# Shield_delitel.net
KiCad netlist of a schematic drawn in Altium Designer
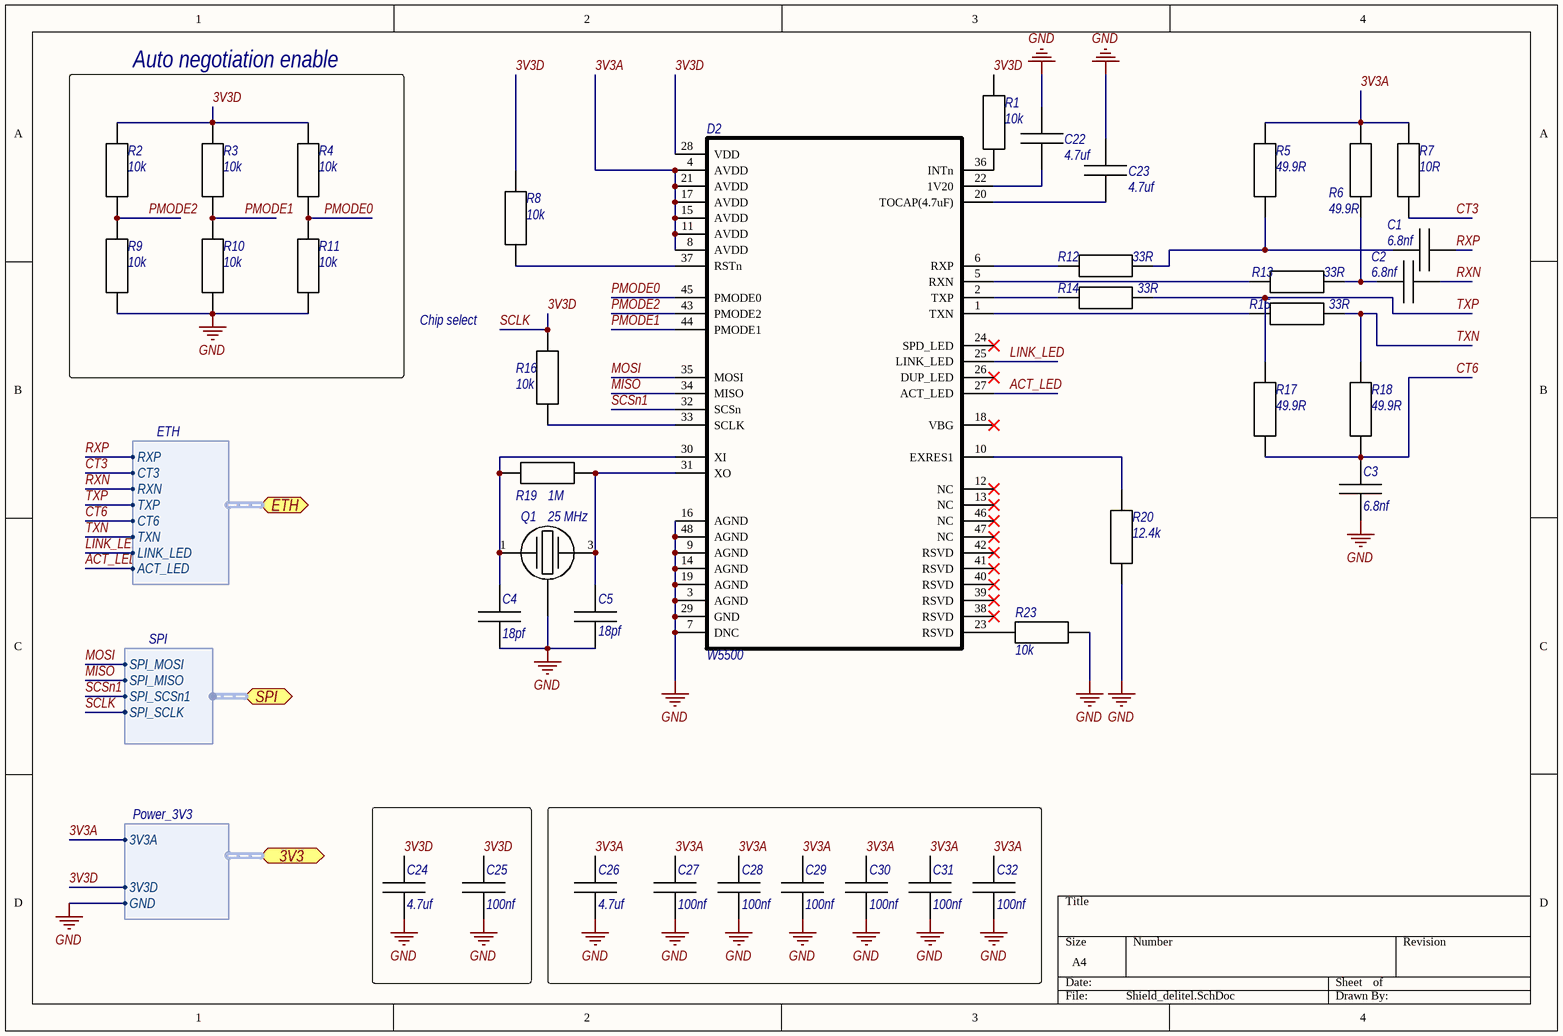
[diagram p0: Shield_delitel.SchDoc]

(export (version "E")
  (design (tool "Eeschema 10.0.6"))
  (components
    (comp (ref "C1") (value "6.8nf") (libsource (lib "Passive") (part "Capacitor")))
    (comp (ref "C2") (value "6.8nf") (libsource (lib "Passive") (part "Capacitor")))
    (comp (ref "C3") (value "6.8nf") (libsource (lib "Passive") (part "Capacitor")))
    (comp (ref "C4") (value "18pf") (libsource (lib "Passive") (part "Capacitor")))
    (comp (ref "C5") (value "18pf") (libsource (lib "Passive") (part "Capacitor")))
    (comp (ref "C22") (value "4.7uf") (libsource (lib "Passive") (part "Capacitor")))
    (comp (ref "C23") (value "4.7uf") (libsource (lib "Passive") (part "Capacitor")))
    (comp (ref "C24") (value "4.7uf") (libsource (lib "Passive") (part "Capacitor")))
    (comp (ref "C25") (value "100nf") (libsource (lib "Passive") (part "Capacitor")))
    (comp (ref "C26") (value "4.7uf") (libsource (lib "Passive") (part "Capacitor")))
    (comp (ref "C27") (value "100nf") (libsource (lib "Passive") (part "Capacitor")))
    (comp (ref "C28") (value "100nf") (libsource (lib "Passive") (part "Capacitor")))
    (comp (ref "C29") (value "100nf") (libsource (lib "Passive") (part "Capacitor")))
    (comp (ref "C30") (value "100nf") (libsource (lib "Passive") (part "Capacitor")))
    (comp (ref "C31") (value "100nf") (libsource (lib "Passive") (part "Capacitor")))
    (comp (ref "C32") (value "100nf") (libsource (lib "Passive") (part "Capacitor")))
    (comp (ref "D2")
      (value "W5500")
      (footprint "LQFP-48 7.0 x 7.0 x 1.6")
      (libsource (lib "ic") (part "W5500"))
    )
    (comp (ref "Q1") (value "25 MHz") (libsource (lib "Passive") (part "Oscillator")))
    (comp (ref "R1") (value "10k") (description "Resistor") (libsource (lib "") (part "Resistor_1")))
    (comp (ref "R2") (value "10k") (description "Resistor") (libsource (lib "") (part "Resistor_1")))
    (comp (ref "R3") (value "10k") (description "Resistor") (libsource (lib "") (part "Resistor_1")))
    (comp (ref "R4") (value "10k") (description "Resistor") (libsource (lib "") (part "Resistor_1")))
    (comp (ref "R5") (value "49.9R") (description "Resistor") (libsource (lib "Passive") (part "Resistor")))
    (comp (ref "R6") (value "49.9R") (description "Resistor") (libsource (lib "Passive") (part "Resistor")))
    (comp (ref "R7") (value "10R") (description "Resistor") (libsource (lib "Passive") (part "Resistor")))
    (comp (ref "R8") (value "10k") (description "Resistor") (libsource (lib "") (part "Resistor_1")))
    (comp (ref "R9") (value "10k") (description "Resistor") (libsource (lib "") (part "Resistor_1")))
    (comp (ref "R10") (value "10k") (description "Resistor") (libsource (lib "") (part "Resistor_1")))
    (comp (ref "R11") (value "10k") (description "Resistor") (libsource (lib "") (part "Resistor_1")))
    (comp (ref "R12") (value "33R") (description "Resistor") (libsource (lib "") (part "Resistor_2")))
    (comp (ref "R13") (value "33R") (description "Resistor") (libsource (lib "") (part "Resistor_2")))
    (comp (ref "R14") (value "33R") (description "Resistor") (libsource (lib "") (part "Resistor_2")))
    (comp (ref "R15") (value "33R") (description "Resistor") (libsource (lib "") (part "Resistor_2")))
    (comp (ref "R16") (value "10k") (description "Resistor") (libsource (lib "Passive") (part "Resistor")))
    (comp (ref "R17") (value "49.9R") (description "Resistor") (libsource (lib "Passive") (part "Resistor")))
    (comp (ref "R18") (value "49.9R") (description "Resistor") (libsource (lib "Passive") (part "Resistor")))
    (comp (ref "R19") (value "1M") (description "Resistor") (libsource (lib "") (part "Resistor_2")))
    (comp (ref "R20") (value "12.4k") (description "Resistor") (libsource (lib "") (part "Resistor_1")))
    (comp (ref "R23") (value "10k") (description "Resistor") (libsource (lib "") (part "Resistor_2")))
  )
  (nets
    (net (code "4") (name "/3V3A") (class "Default")
      (node (ref "C26") (pin "2") (pinfunction "2_2") (pintype "passive"))
      (node (ref "C27") (pin "2") (pinfunction "2_2") (pintype "passive"))
      (node (ref "C28") (pin "2") (pinfunction "2_2") (pintype "passive"))
      (node (ref "C29") (pin "2") (pinfunction "2_2") (pintype "passive"))
      (node (ref "C30") (pin "2") (pinfunction "2_2") (pintype "passive"))
      (node (ref "C31") (pin "2") (pinfunction "2_2") (pintype "passive"))
      (node (ref "C32") (pin "2") (pinfunction "2_2") (pintype "passive"))
      (node (ref "D2") (pin "11") (pinfunction "AVDD_11") (pintype "passive"))
      (node (ref "D2") (pin "15") (pinfunction "AVDD_15") (pintype "passive"))
      (node (ref "D2") (pin "17") (pinfunction "AVDD_17") (pintype "passive"))
      (node (ref "D2") (pin "21") (pinfunction "AVDD_21") (pintype "passive"))
      (node (ref "D2") (pin "4") (pinfunction "AVDD_4") (pintype "passive"))
      (node (ref "D2") (pin "8") (pinfunction "AVDD_8") (pintype "passive"))
      (node (ref "R5") (pin "1") (pinfunction "1_1") (pintype "passive"))
      (node (ref "R6") (pin "1") (pinfunction "1_1") (pintype "passive"))
      (node (ref "R7") (pin "1") (pinfunction "1_1") (pintype "passive"))
    )
    (net (code "5") (name "/3V3D") (class "Default")
      (node (ref "C24") (pin "2") (pinfunction "2_2") (pintype "passive"))
      (node (ref "C25") (pin "2") (pinfunction "2_2") (pintype "passive"))
      (node (ref "D2") (pin "28") (pinfunction "VDD_28") (pintype "passive"))
      (node (ref "R1") (pin "2") (pinfunction "2_2") (pintype "passive"))
      (node (ref "R16") (pin "1") (pinfunction "1_1") (pintype "passive"))
      (node (ref "R2") (pin "2") (pinfunction "2_2") (pintype "passive"))
      (node (ref "R3") (pin "2") (pinfunction "2_2") (pintype "passive"))
      (node (ref "R4") (pin "2") (pinfunction "2_2") (pintype "passive"))
      (node (ref "R8") (pin "2") (pinfunction "2_2") (pintype "passive"))
    )
    (net (code "6") (name "/ACT_LED") (class "Default")
      (node (ref "D2") (pin "27") (pinfunction "ACT_LED_27") (pintype "passive"))
    )
    (net (code "7") (name "/CT3") (class "Default")
      (node (ref "R7") (pin "2") (pinfunction "2_2") (pintype "passive"))
    )
    (net (code "8") (name "/CT6") (class "Default")
      (node (ref "C3") (pin "2") (pinfunction "2_2") (pintype "passive"))
      (node (ref "R17") (pin "2") (pinfunction "2_2") (pintype "passive"))
      (node (ref "R18") (pin "2") (pinfunction "2_2") (pintype "passive"))
    )
    (net (code "9") (name "/LINK_LED") (class "Default")
      (node (ref "D2") (pin "25") (pinfunction "LINK_LED_25") (pintype "passive"))
    )
    (net (code "10") (name "/MISO") (class "Default")
      (node (ref "D2") (pin "34") (pinfunction "MISO_34") (pintype "passive"))
    )
    (net (code "11") (name "/MOSI") (class "Default")
      (node (ref "D2") (pin "35") (pinfunction "MOSI_35") (pintype "passive"))
    )
    (net (code "12") (name "/PMODE0") (class "Default")
      (node (ref "D2") (pin "45") (pinfunction "PMODE0_45") (pintype "passive"))
      (node (ref "R11") (pin "2") (pinfunction "2_2") (pintype "passive"))
      (node (ref "R4") (pin "1") (pinfunction "1_1") (pintype "passive"))
    )
    (net (code "13") (name "/PMODE1") (class "Default")
      (node (ref "D2") (pin "44") (pinfunction "PMODE1_44") (pintype "passive"))
      (node (ref "R10") (pin "2") (pinfunction "2_2") (pintype "passive"))
      (node (ref "R3") (pin "1") (pinfunction "1_1") (pintype "passive"))
    )
    (net (code "14") (name "/PMODE2") (class "Default")
      (node (ref "D2") (pin "43") (pinfunction "PMODE2_43") (pintype "passive"))
      (node (ref "R2") (pin "1") (pinfunction "1_1") (pintype "passive"))
      (node (ref "R9") (pin "2") (pinfunction "2_2") (pintype "passive"))
    )
    (net (code "15") (name "/RXN") (class "Default")
      (node (ref "C2") (pin "1") (pinfunction "1_1") (pintype "passive"))
    )
    (net (code "16") (name "/RXP") (class "Default")
      (node (ref "C1") (pin "1") (pinfunction "1_1") (pintype "passive"))
    )
    (net (code "17") (name "/SCSn1") (class "Default")
      (node (ref "D2") (pin "32") (pinfunction "SCSn_32") (pintype "passive"))
    )
    (net (code "18") (name "/TXN") (class "Default")
      (node (ref "R15") (pin "1") (pinfunction "1_1") (pintype "passive"))
      (node (ref "R18") (pin "1") (pinfunction "1_1") (pintype "passive"))
    )
    (net (code "19") (name "/TXP") (class "Default")
      (node (ref "R14") (pin "1") (pinfunction "1_1") (pintype "passive"))
      (node (ref "R17") (pin "1") (pinfunction "1_1") (pintype "passive"))
    )
    (net (code "23") (name "GND") (class "Default")
      (node (ref "C22") (pin "1") (pinfunction "1_1") (pintype "passive"))
      (node (ref "C23") (pin "1") (pinfunction "1_1") (pintype "passive"))
      (node (ref "C24") (pin "1") (pinfunction "1_1") (pintype "passive"))
      (node (ref "C25") (pin "1") (pinfunction "1_1") (pintype "passive"))
      (node (ref "C26") (pin "1") (pinfunction "1_1") (pintype "passive"))
      (node (ref "C27") (pin "1") (pinfunction "1_1") (pintype "passive"))
      (node (ref "C28") (pin "1") (pinfunction "1_1") (pintype "passive"))
      (node (ref "C29") (pin "1") (pinfunction "1_1") (pintype "passive"))
      (node (ref "C3") (pin "1") (pinfunction "1_1") (pintype "passive"))
      (node (ref "C30") (pin "1") (pinfunction "1_1") (pintype "passive"))
      (node (ref "C31") (pin "1") (pinfunction "1_1") (pintype "passive"))
      (node (ref "C32") (pin "1") (pinfunction "1_1") (pintype "passive"))
      (node (ref "C4") (pin "1") (pinfunction "1_1") (pintype "passive"))
      (node (ref "C5") (pin "1") (pinfunction "1_1") (pintype "passive"))
      (node (ref "D2") (pin "14") (pinfunction "AGND_14") (pintype "passive"))
      (node (ref "D2") (pin "16") (pinfunction "AGND_16") (pintype "passive"))
      (node (ref "D2") (pin "19") (pinfunction "AGND_19") (pintype "passive"))
      (node (ref "D2") (pin "29") (pinfunction "GND_29") (pintype "passive"))
      (node (ref "D2") (pin "3") (pinfunction "AGND_3") (pintype "passive"))
      (node (ref "D2") (pin "48") (pinfunction "AGND_48") (pintype "passive"))
      (node (ref "D2") (pin "7") (pinfunction "DNC_7") (pintype "passive"))
      (node (ref "D2") (pin "9") (pinfunction "AGND_9") (pintype "passive"))
      (node (ref "Q1") (pin "2") (pinfunction "2_2") (pintype "passive"))
      (node (ref "Q1") (pin "4") (pinfunction "4_4") (pintype "passive"))
      (node (ref "R10") (pin "1") (pinfunction "1_1") (pintype "passive"))
      (node (ref "R11") (pin "1") (pinfunction "1_1") (pintype "passive"))
      (node (ref "R20") (pin "1") (pinfunction "1_1") (pintype "passive"))
      (node (ref "R23") (pin "1") (pinfunction "1_1") (pintype "passive"))
      (node (ref "R9") (pin "1") (pinfunction "1_1") (pintype "passive"))
    )
    (net (code "24") (name "Net-(C1-Pad2)") (class "Default")
      (node (ref "C1") (pin "2") (pinfunction "2_2") (pintype "passive"))
      (node (ref "R12") (pin "1") (pinfunction "1_1") (pintype "passive"))
      (node (ref "R5") (pin "2") (pinfunction "2_2") (pintype "passive"))
    )
    (net (code "25") (name "Net-(C2-Pad2)") (class "Default")
      (node (ref "C2") (pin "2") (pinfunction "2_2") (pintype "passive"))
      (node (ref "R13") (pin "1") (pinfunction "1_1") (pintype "passive"))
      (node (ref "R6") (pin "2") (pinfunction "2_2") (pintype "passive"))
    )
    (net (code "26") (name "Net-(D2-1V20)") (class "Default")
      (node (ref "C22") (pin "2") (pinfunction "2_2") (pintype "passive"))
      (node (ref "D2") (pin "22") (pinfunction "1V20_22") (pintype "passive"))
    )
    (net (code "27") (name "Net-(D2-EXRES1)") (class "Default")
      (node (ref "D2") (pin "10") (pinfunction "EXRES1_10") (pintype "passive"))
      (node (ref "R20") (pin "2") (pinfunction "2_2") (pintype "passive"))
    )
    (net (code "28") (name "Net-(D2-INTn)") (class "Default")
      (node (ref "D2") (pin "36") (pinfunction "INTn_36") (pintype "passive"))
      (node (ref "R1") (pin "1") (pinfunction "1_1") (pintype "passive"))
    )
    (net (code "29") (name "Net-(D2-RSTn)") (class "Default")
      (node (ref "D2") (pin "37") (pinfunction "RSTn_37") (pintype "passive"))
      (node (ref "R8") (pin "1") (pinfunction "1_1") (pintype "passive"))
    )
    (net (code "30") (name "Net-(D2-RSVD-Pad23)") (class "Default")
      (node (ref "D2") (pin "23") (pinfunction "RSVD_23") (pintype "passive"))
      (node (ref "R23") (pin "2") (pinfunction "2_2") (pintype "passive"))
    )
    (net (code "31") (name "Net-(D2-RXN)") (class "Default")
      (node (ref "D2") (pin "5") (pinfunction "RXN_5") (pintype "passive"))
      (node (ref "R13") (pin "2") (pinfunction "2_2") (pintype "passive"))
    )
    (net (code "32") (name "Net-(D2-RXP)") (class "Default")
      (node (ref "D2") (pin "6") (pinfunction "RXP_6") (pintype "passive"))
      (node (ref "R12") (pin "2") (pinfunction "2_2") (pintype "passive"))
    )
    (net (code "33") (name "Net-(D2-SCLK)") (class "Default")
      (node (ref "D2") (pin "33") (pinfunction "SCLK_33") (pintype "passive"))
      (node (ref "R16") (pin "2") (pinfunction "2_2") (pintype "passive"))
    )
    (net (code "34") (name "Net-(D2-TOCAP(4.7uF))") (class "Default")
      (node (ref "C23") (pin "2") (pinfunction "2_2") (pintype "passive"))
      (node (ref "D2") (pin "20") (pinfunction "TOCAP(4.7uF)_20") (pintype "passive"))
    )
    (net (code "35") (name "Net-(D2-TXN)") (class "Default")
      (node (ref "D2") (pin "1") (pinfunction "TXN_1") (pintype "passive"))
      (node (ref "R15") (pin "2") (pinfunction "2_2") (pintype "passive"))
    )
    (net (code "36") (name "Net-(D2-TXP)") (class "Default")
      (node (ref "D2") (pin "2") (pinfunction "TXP_2") (pintype "passive"))
      (node (ref "R14") (pin "2") (pinfunction "2_2") (pintype "passive"))
    )
    (net (code "37") (name "Net-(D2-XI)") (class "Default")
      (node (ref "C4") (pin "2") (pinfunction "2_2") (pintype "passive"))
      (node (ref "D2") (pin "30") (pinfunction "XI_30") (pintype "passive"))
      (node (ref "Q1") (pin "1") (pinfunction "1_1") (pintype "passive"))
      (node (ref "R19") (pin "2") (pinfunction "2_2") (pintype "passive"))
    )
    (net (code "38") (name "Net-(D2-XO)") (class "Default")
      (node (ref "C5") (pin "2") (pinfunction "2_2") (pintype "passive"))
      (node (ref "D2") (pin "31") (pinfunction "XO_31") (pintype "passive"))
      (node (ref "Q1") (pin "3") (pinfunction "3_3") (pintype "passive"))
      (node (ref "R19") (pin "1") (pinfunction "1_1") (pintype "passive"))
    )
    (net (code "39") (name "unconnected-(D2-DUP_LED-Pad26)") (class "Default")
      (node (ref "D2") (pin "26") (pinfunction "DUP_LED_26") (pintype "passive+no_connect"))
    )
    (net (code "40") (name "unconnected-(D2-NC-Pad12)") (class "Default")
      (node (ref "D2") (pin "12") (pinfunction "NC_12") (pintype "passive+no_connect"))
    )
    (net (code "41") (name "unconnected-(D2-NC-Pad13)") (class "Default")
      (node (ref "D2") (pin "13") (pinfunction "NC_13") (pintype "passive+no_connect"))
    )
    (net (code "42") (name "unconnected-(D2-NC-Pad46)") (class "Default")
      (node (ref "D2") (pin "46") (pinfunction "NC_46") (pintype "passive+no_connect"))
    )
    (net (code "43") (name "unconnected-(D2-NC-Pad47)") (class "Default")
      (node (ref "D2") (pin "47") (pinfunction "NC_47") (pintype "passive+no_connect"))
    )
    (net (code "44") (name "unconnected-(D2-RSVD-Pad38)") (class "Default")
      (node (ref "D2") (pin "38") (pinfunction "RSVD_38") (pintype "passive+no_connect"))
    )
    (net (code "45") (name "unconnected-(D2-RSVD-Pad39)") (class "Default")
      (node (ref "D2") (pin "39") (pinfunction "RSVD_39") (pintype "passive+no_connect"))
    )
    (net (code "46") (name "unconnected-(D2-RSVD-Pad40)") (class "Default")
      (node (ref "D2") (pin "40") (pinfunction "RSVD_40") (pintype "passive+no_connect"))
    )
    (net (code "47") (name "unconnected-(D2-RSVD-Pad41)") (class "Default")
      (node (ref "D2") (pin "41") (pinfunction "RSVD_41") (pintype "passive+no_connect"))
    )
    (net (code "48") (name "unconnected-(D2-RSVD-Pad42)") (class "Default")
      (node (ref "D2") (pin "42") (pinfunction "RSVD_42") (pintype "passive+no_connect"))
    )
    (net (code "49") (name "unconnected-(D2-SPD_LED-Pad24)") (class "Default")
      (node (ref "D2") (pin "24") (pinfunction "SPD_LED_24") (pintype "passive+no_connect"))
    )
    (net (code "50") (name "unconnected-(D2-VBG-Pad18)") (class "Default")
      (node (ref "D2") (pin "18") (pinfunction "VBG_18") (pintype "passive+no_connect"))
    )
  )
)
